# BreakoutShieldRevB.net
KiCad netlist of a schematic drawn in EAGLE
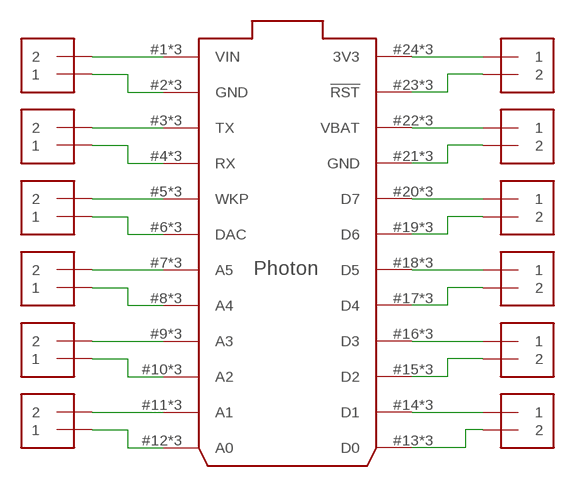
[diagram p0: schematic, sheet 1]

(export (version "E")
  (design (tool "Eeschema 10.0.6"))
  (components
    (comp (ref "J1")
      (value "1X2-3.5MM")
      (footprint "eagle-import:1X2-3.5MM")
      (libsource (lib "eagle-import") (part "1X2-3.5MM"))
    )
    (comp (ref "J2")
      (value "1X2-3.5MM")
      (footprint "eagle-import:1X2-3.5MM")
      (libsource (lib "eagle-import") (part "1X2-3.5MM"))
    )
    (comp (ref "J3")
      (value "1X2-3.5MM")
      (footprint "eagle-import:1X2-3.5MM")
      (libsource (lib "eagle-import") (part "1X2-3.5MM"))
    )
    (comp (ref "J4")
      (value "1X2-3.5MM")
      (footprint "eagle-import:1X2-3.5MM")
      (libsource (lib "eagle-import") (part "1X2-3.5MM"))
    )
    (comp (ref "J5")
      (value "1X2-3.5MM")
      (footprint "eagle-import:1X2-3.5MM")
      (libsource (lib "eagle-import") (part "1X2-3.5MM"))
    )
    (comp (ref "J6")
      (value "1X2-3.5MM")
      (footprint "eagle-import:1X2-3.5MM")
      (libsource (lib "eagle-import") (part "1X2-3.5MM"))
    )
    (comp (ref "J7")
      (value "1X2-3.5MM")
      (footprint "eagle-import:1X2-3.5MM")
      (libsource (lib "eagle-import") (part "1X2-3.5MM"))
    )
    (comp (ref "J8")
      (value "1X2-3.5MM")
      (footprint "eagle-import:1X2-3.5MM")
      (libsource (lib "eagle-import") (part "1X2-3.5MM"))
    )
    (comp (ref "J9")
      (value "1X2-3.5MM")
      (footprint "eagle-import:1X2-3.5MM")
      (libsource (lib "eagle-import") (part "1X2-3.5MM"))
    )
    (comp (ref "J10")
      (value "1X2-3.5MM")
      (footprint "eagle-import:1X2-3.5MM")
      (libsource (lib "eagle-import") (part "1X2-3.5MM"))
    )
    (comp (ref "J11")
      (value "1X2-3.5MM")
      (footprint "eagle-import:1X2-3.5MM")
      (libsource (lib "eagle-import") (part "1X2-3.5MM"))
    )
    (comp (ref "J12")
      (value "1X2-3.5MM")
      (footprint "eagle-import:1X2-3.5MM")
      (libsource (lib "eagle-import") (part "1X2-3.5MM"))
    )
    (comp (ref "U$1")
      (value "PHOTON_WITH_STACKABLE_HEADERS")
      (footprint "eagle-import:PHOTON_STACKABLE")
      (libsource (lib "eagle-import") (part "PHOTON_WITH_STACKABLE_HEADERS"))
    )
  )
  (nets
    (net (code "1") (name "Net-(J1-Pad1)") (class "Default")
      (node (ref "J1") (pin "1") (pinfunction "1_1") (pintype "passive"))
      (node (ref "U$1") (pin "#2") (pinfunction "GND_#2") (pintype "power_in"))
      (node (ref "U$1") (pin "2") (pinfunction "GND_2") (pintype "power_in"))
      (node (ref "U$1") (pin "@2") (pinfunction "GND_@2") (pintype "power_in"))
    )
    (net (code "2") (name "Net-(J1-Pad2)") (class "Default")
      (node (ref "J1") (pin "2") (pinfunction "2_2") (pintype "passive"))
      (node (ref "U$1") (pin "#1") (pinfunction "VIN_#1") (pintype "power_in"))
      (node (ref "U$1") (pin "1") (pinfunction "VIN_1") (pintype "power_in"))
      (node (ref "U$1") (pin "@1") (pinfunction "VIN_@1") (pintype "power_in"))
    )
    (net (code "3") (name "Net-(J2-Pad1)") (class "Default")
      (node (ref "J2") (pin "1") (pinfunction "1_1") (pintype "passive"))
      (node (ref "U$1") (pin "#4") (pinfunction "RX_#4") (pintype "bidirectional"))
      (node (ref "U$1") (pin "4") (pinfunction "RX_4") (pintype "bidirectional"))
      (node (ref "U$1") (pin "@4") (pinfunction "RX_@4") (pintype "bidirectional"))
    )
    (net (code "4") (name "Net-(J2-Pad2)") (class "Default")
      (node (ref "J2") (pin "2") (pinfunction "2_2") (pintype "passive"))
      (node (ref "U$1") (pin "#3") (pinfunction "TX_#3") (pintype "bidirectional"))
      (node (ref "U$1") (pin "3") (pinfunction "TX_3") (pintype "bidirectional"))
      (node (ref "U$1") (pin "@3") (pinfunction "TX_@3") (pintype "bidirectional"))
    )
    (net (code "5") (name "Net-(J3-Pad1)") (class "Default")
      (node (ref "J3") (pin "1") (pinfunction "1_1") (pintype "passive"))
      (node (ref "U$1") (pin "#6") (pinfunction "DAC_#6") (pintype "bidirectional"))
      (node (ref "U$1") (pin "6") (pinfunction "DAC_6") (pintype "bidirectional"))
      (node (ref "U$1") (pin "@6") (pinfunction "DAC_@6") (pintype "bidirectional"))
    )
    (net (code "6") (name "Net-(J3-Pad2)") (class "Default")
      (node (ref "J3") (pin "2") (pinfunction "2_2") (pintype "passive"))
      (node (ref "U$1") (pin "#5") (pinfunction "WKP_#5") (pintype "bidirectional"))
      (node (ref "U$1") (pin "5") (pinfunction "WKP_5") (pintype "bidirectional"))
      (node (ref "U$1") (pin "@5") (pinfunction "WKP_@5") (pintype "bidirectional"))
    )
    (net (code "7") (name "Net-(J4-Pad1)") (class "Default")
      (node (ref "J4") (pin "1") (pinfunction "1_1") (pintype "passive"))
      (node (ref "U$1") (pin "#8") (pinfunction "A4_#8") (pintype "bidirectional"))
      (node (ref "U$1") (pin "8") (pinfunction "A4_8") (pintype "bidirectional"))
      (node (ref "U$1") (pin "@8") (pinfunction "A4_@8") (pintype "bidirectional"))
    )
    (net (code "8") (name "Net-(J4-Pad2)") (class "Default")
      (node (ref "J4") (pin "2") (pinfunction "2_2") (pintype "passive"))
      (node (ref "U$1") (pin "#7") (pinfunction "A5_#7") (pintype "bidirectional"))
      (node (ref "U$1") (pin "7") (pinfunction "A5_7") (pintype "bidirectional"))
      (node (ref "U$1") (pin "@7") (pinfunction "A5_@7") (pintype "bidirectional"))
    )
    (net (code "9") (name "Net-(J5-Pad1)") (class "Default")
      (node (ref "J5") (pin "1") (pinfunction "1_1") (pintype "passive"))
      (node (ref "U$1") (pin "#10") (pinfunction "A2_#10") (pintype "bidirectional"))
      (node (ref "U$1") (pin "10") (pinfunction "A2_10") (pintype "bidirectional"))
      (node (ref "U$1") (pin "@10") (pinfunction "A2_@10") (pintype "bidirectional"))
    )
    (net (code "10") (name "Net-(J5-Pad2)") (class "Default")
      (node (ref "J5") (pin "2") (pinfunction "2_2") (pintype "passive"))
      (node (ref "U$1") (pin "#9") (pinfunction "A3_#9") (pintype "bidirectional"))
      (node (ref "U$1") (pin "9") (pinfunction "A3_9") (pintype "bidirectional"))
      (node (ref "U$1") (pin "@9") (pinfunction "A3_@9") (pintype "bidirectional"))
    )
    (net (code "11") (name "Net-(J6-Pad1)") (class "Default")
      (node (ref "J6") (pin "1") (pinfunction "1_1") (pintype "passive"))
      (node (ref "U$1") (pin "#12") (pinfunction "A0_#12") (pintype "bidirectional"))
      (node (ref "U$1") (pin "12") (pinfunction "A0_12") (pintype "bidirectional"))
      (node (ref "U$1") (pin "@12") (pinfunction "A0_@12") (pintype "bidirectional"))
    )
    (net (code "12") (name "Net-(J6-Pad2)") (class "Default")
      (node (ref "J6") (pin "2") (pinfunction "2_2") (pintype "passive"))
      (node (ref "U$1") (pin "#11") (pinfunction "A1_#11") (pintype "bidirectional"))
      (node (ref "U$1") (pin "11") (pinfunction "A1_11") (pintype "bidirectional"))
      (node (ref "U$1") (pin "@11") (pinfunction "A1_@11") (pintype "bidirectional"))
    )
    (net (code "13") (name "Net-(J7-Pad1)") (class "Default")
      (node (ref "J7") (pin "1") (pinfunction "1_1") (pintype "passive"))
      (node (ref "U$1") (pin "#24") (pinfunction "3V3_#24") (pintype "power_in"))
      (node (ref "U$1") (pin "24") (pinfunction "3V3_24") (pintype "power_in"))
      (node (ref "U$1") (pin "@24") (pinfunction "3V3_@24") (pintype "power_in"))
    )
    (net (code "14") (name "Net-(J7-Pad2)") (class "Default")
      (node (ref "J7") (pin "2") (pinfunction "2_2") (pintype "passive"))
      (node (ref "U$1") (pin "#23") (pinfunction "~{RST}_#23") (pintype "bidirectional"))
      (node (ref "U$1") (pin "23") (pinfunction "~{RST}_23") (pintype "bidirectional"))
      (node (ref "U$1") (pin "@23") (pinfunction "~{RST}_@23") (pintype "bidirectional"))
    )
    (net (code "15") (name "Net-(J8-Pad1)") (class "Default")
      (node (ref "J8") (pin "1") (pinfunction "1_1") (pintype "passive"))
      (node (ref "U$1") (pin "#22") (pinfunction "VBAT_#22") (pintype "power_in"))
      (node (ref "U$1") (pin "22") (pinfunction "VBAT_22") (pintype "power_in"))
      (node (ref "U$1") (pin "@22") (pinfunction "VBAT_@22") (pintype "power_in"))
    )
    (net (code "16") (name "Net-(J8-Pad2)") (class "Default")
      (node (ref "J8") (pin "2") (pinfunction "2_2") (pintype "passive"))
      (node (ref "U$1") (pin "#21") (pinfunction "GND_#21") (pintype "power_in"))
      (node (ref "U$1") (pin "21") (pinfunction "GND_21") (pintype "power_in"))
      (node (ref "U$1") (pin "@21") (pinfunction "GND_@21") (pintype "power_in"))
    )
    (net (code "17") (name "Net-(J9-Pad1)") (class "Default")
      (node (ref "J9") (pin "1") (pinfunction "1_1") (pintype "passive"))
      (node (ref "U$1") (pin "#20") (pinfunction "D7_#20") (pintype "bidirectional"))
      (node (ref "U$1") (pin "20") (pinfunction "D7_20") (pintype "bidirectional"))
      (node (ref "U$1") (pin "@20") (pinfunction "D7_@20") (pintype "bidirectional"))
    )
    (net (code "18") (name "Net-(J9-Pad2)") (class "Default")
      (node (ref "J9") (pin "2") (pinfunction "2_2") (pintype "passive"))
      (node (ref "U$1") (pin "#19") (pinfunction "D6_#19") (pintype "bidirectional"))
      (node (ref "U$1") (pin "19") (pinfunction "D6_19") (pintype "bidirectional"))
      (node (ref "U$1") (pin "@19") (pinfunction "D6_@19") (pintype "bidirectional"))
    )
    (net (code "19") (name "Net-(J10-Pad1)") (class "Default")
      (node (ref "J10") (pin "1") (pinfunction "1_1") (pintype "passive"))
      (node (ref "U$1") (pin "#18") (pinfunction "D5_#18") (pintype "bidirectional"))
      (node (ref "U$1") (pin "18") (pinfunction "D5_18") (pintype "bidirectional"))
      (node (ref "U$1") (pin "@18") (pinfunction "D5_@18") (pintype "bidirectional"))
    )
    (net (code "20") (name "Net-(J10-Pad2)") (class "Default")
      (node (ref "J10") (pin "2") (pinfunction "2_2") (pintype "passive"))
      (node (ref "U$1") (pin "#17") (pinfunction "D4_#17") (pintype "bidirectional"))
      (node (ref "U$1") (pin "17") (pinfunction "D4_17") (pintype "bidirectional"))
      (node (ref "U$1") (pin "@17") (pinfunction "D4_@17") (pintype "bidirectional"))
    )
    (net (code "21") (name "Net-(J11-Pad1)") (class "Default")
      (node (ref "J11") (pin "1") (pinfunction "1_1") (pintype "passive"))
      (node (ref "U$1") (pin "#16") (pinfunction "D3_#16") (pintype "bidirectional"))
      (node (ref "U$1") (pin "16") (pinfunction "D3_16") (pintype "bidirectional"))
      (node (ref "U$1") (pin "@16") (pinfunction "D3_@16") (pintype "bidirectional"))
    )
    (net (code "22") (name "Net-(J11-Pad2)") (class "Default")
      (node (ref "J11") (pin "2") (pinfunction "2_2") (pintype "passive"))
      (node (ref "U$1") (pin "#15") (pinfunction "D2_#15") (pintype "bidirectional"))
      (node (ref "U$1") (pin "15") (pinfunction "D2_15") (pintype "bidirectional"))
      (node (ref "U$1") (pin "@15") (pinfunction "D2_@15") (pintype "bidirectional"))
    )
    (net (code "23") (name "Net-(J12-Pad1)") (class "Default")
      (node (ref "J12") (pin "1") (pinfunction "1_1") (pintype "passive"))
      (node (ref "U$1") (pin "#14") (pinfunction "D1_#14") (pintype "bidirectional"))
      (node (ref "U$1") (pin "14") (pinfunction "D1_14") (pintype "bidirectional"))
      (node (ref "U$1") (pin "@14") (pinfunction "D1_@14") (pintype "bidirectional"))
    )
    (net (code "24") (name "Net-(J12-Pad2)") (class "Default")
      (node (ref "J12") (pin "2") (pinfunction "2_2") (pintype "passive"))
      (node (ref "U$1") (pin "#13") (pinfunction "D0_#13") (pintype "bidirectional"))
      (node (ref "U$1") (pin "13") (pinfunction "D0_13") (pintype "bidirectional"))
      (node (ref "U$1") (pin "@13") (pinfunction "D0_@13") (pintype "bidirectional"))
    )
  )
)
